# Sheet1.net
KiCad netlist of a schematic drawn in Altium Designer
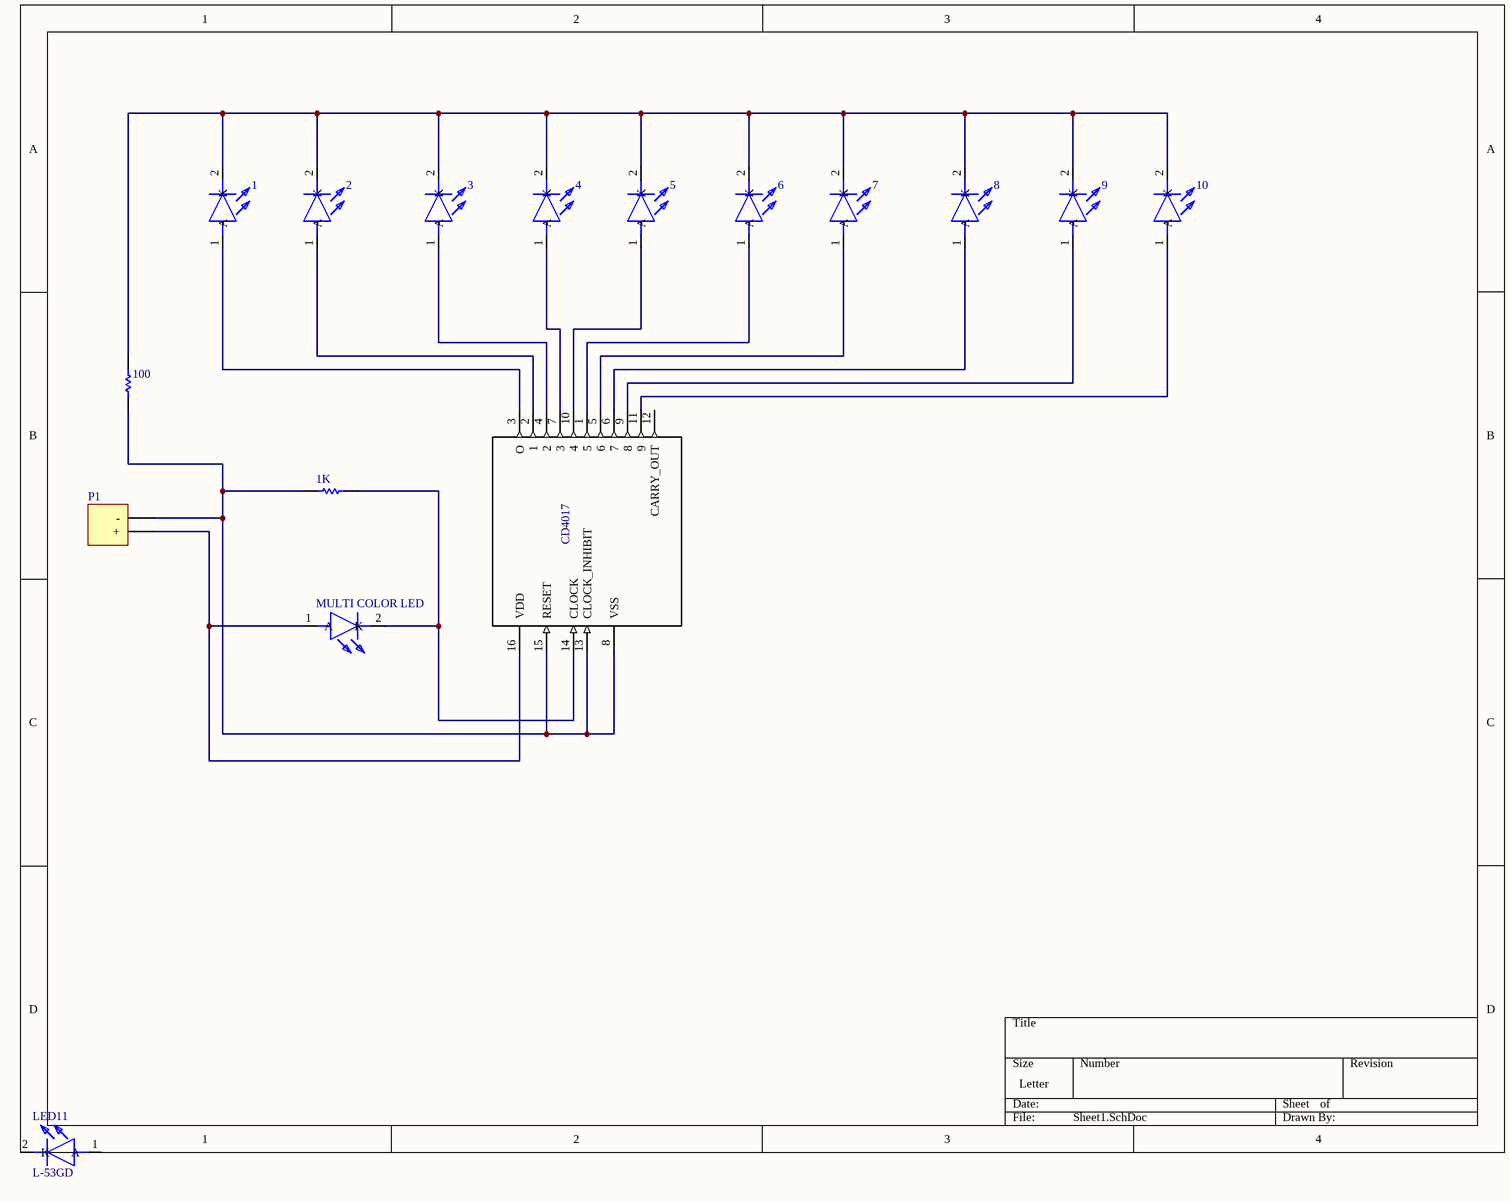
[diagram p0: Sheet1.SchDoc]

(export (version "E")
  (design (tool "Eeschema 10.0.6"))
  (components
    (comp (ref "1")
      (value "L-53GD")
      (footprint "SamacSys:L-53GD")
      (description "LED")
      (fields (field (name "RS PART NUMBER") "2286004A"))
      (libsource (lib "SamacSys") (part "L-53GD"))
    )
    (comp (ref "1K")
      (value "Res1")
      (footprint "AXIAL-0.3")
      (description "Resistor")
      (fields (field (name "PUBLISHER") "Altium Limited"))
      (libsource (lib "Miscellaneous Devices") (part "Res1"))
    )
    (comp (ref "2")
      (value "L-53GD")
      (footprint "SamacSys:L-53GD")
      (description "LED")
      (fields (field (name "RS PART NUMBER") "2286004A"))
      (libsource (lib "SamacSys") (part "L-53GD"))
    )
    (comp (ref "3")
      (value "L-53GD")
      (footprint "SamacSys:L-53GD")
      (description "LED")
      (fields (field (name "RS PART NUMBER") "2286004A"))
      (libsource (lib "SamacSys") (part "L-53GD"))
    )
    (comp (ref "4")
      (value "L-53GD")
      (footprint "SamacSys:L-53GD")
      (description "LED")
      (fields (field (name "RS PART NUMBER") "2286004A"))
      (libsource (lib "SamacSys") (part "L-53GD"))
    )
    (comp (ref "5")
      (value "L-53GD")
      (footprint "SamacSys:L-53GD")
      (description "LED")
      (fields (field (name "RS PART NUMBER") "2286004A"))
      (libsource (lib "SamacSys") (part "L-53GD"))
    )
    (comp (ref "6")
      (value "L-53GD")
      (footprint "SamacSys:L-53GD")
      (description "LED")
      (fields (field (name "RS PART NUMBER") "2286004A"))
      (libsource (lib "SamacSys") (part "L-53GD"))
    )
    (comp (ref "7")
      (value "L-53GD")
      (footprint "SamacSys:L-53GD")
      (description "LED")
      (fields (field (name "RS PART NUMBER") "2286004A"))
      (libsource (lib "SamacSys") (part "L-53GD"))
    )
    (comp (ref "8")
      (value "L-53GD")
      (footprint "SamacSys:L-53GD")
      (description "LED")
      (fields (field (name "RS PART NUMBER") "2286004A"))
      (libsource (lib "SamacSys") (part "L-53GD"))
    )
    (comp (ref "9")
      (value "L-53GD")
      (footprint "SamacSys:L-53GD")
      (description "LED")
      (fields (field (name "RS PART NUMBER") "2286004A"))
      (libsource (lib "SamacSys") (part "L-53GD"))
    )
    (comp (ref "10")
      (value "L-53GD")
      (footprint "SamacSys:L-53GD")
      (description "LED")
      (fields (field (name "RS PART NUMBER") "2286004A"))
      (libsource (lib "SamacSys") (part "L-53GD"))
    )
    (comp (ref "100")
      (value "Res1")
      (footprint "AXIAL-0.3")
      (description "Resistor")
      (fields (field (name "PUBLISHER") "Altium Limited"))
      (libsource (lib "Miscellaneous Devices") (part "Res1"))
    )
    (comp (ref "CD4017")
      (value "CD4017BE")
      (footprint "*DIP254P762X508-16")
      (description "IC Mos 4017/CD4017BE HARRIS")
      (fields (field (name "MF") "Texas"))
      (libsource (lib "CD4017BE") (part "CD4017BE"))
    )
    (comp (ref "LED11")
      (value "L-53GD")
      (footprint "SamacSys:L-53GD")
      (description "LED")
      (fields (field (name "RS PART NUMBER") "2286004A"))
      (libsource (lib "*") (part "L-53GD"))
    )
    (comp (ref "MULTI COLOR LED")
      (value "L-53GD")
      (footprint "SamacSys:L-53GD")
      (description "LED")
      (fields (field (name "RS PART NUMBER") "2286004A"))
      (libsource (lib "SamacSys") (part "L-53GD"))
    )
    (comp (ref "P1")
      (value "Header 2")
      (footprint "HDR1X2")
      (description "Header, 2-Pin")
      (fields (field (name "PUBLISHER") "Altium Limited"))
      (libsource (lib "Miscellaneous Connectors") (part "Header 2"))
    )
  )
  (nets
    (net (code "1") (name "Net-(1-A)") (class "Default")
      (node (ref "1") (pin "1") (pinfunction "A_1") (pintype "passive"))
      (node (ref "CD4017") (pin "3") (pinfunction "O_3") (pintype "output"))
    )
    (net (code "2") (name "Net-(1-K)") (class "Default")
      (node (ref "1") (pin "2") (pinfunction "K_2") (pintype "passive"))
      (node (ref "10") (pin "2") (pinfunction "K_2") (pintype "passive"))
      (node (ref "100") (pin "2") (pinfunction "2_2") (pintype "passive"))
      (node (ref "2") (pin "2") (pinfunction "K_2") (pintype "passive"))
      (node (ref "3") (pin "2") (pinfunction "K_2") (pintype "passive"))
      (node (ref "4") (pin "2") (pinfunction "K_2") (pintype "passive"))
      (node (ref "5") (pin "2") (pinfunction "K_2") (pintype "passive"))
      (node (ref "6") (pin "2") (pinfunction "K_2") (pintype "passive"))
      (node (ref "7") (pin "2") (pinfunction "K_2") (pintype "passive"))
      (node (ref "8") (pin "2") (pinfunction "K_2") (pintype "passive"))
      (node (ref "9") (pin "2") (pinfunction "K_2") (pintype "passive"))
    )
    (net (code "3") (name "Net-(2-A)") (class "Default")
      (node (ref "2") (pin "1") (pinfunction "A_1") (pintype "passive"))
      (node (ref "CD4017") (pin "2") (pinfunction "1_2") (pintype "output"))
    )
    (net (code "4") (name "Net-(3-A)") (class "Default")
      (node (ref "3") (pin "1") (pinfunction "A_1") (pintype "passive"))
      (node (ref "CD4017") (pin "4") (pinfunction "2_4") (pintype "output"))
    )
    (net (code "5") (name "Net-(4-A)") (class "Default")
      (node (ref "4") (pin "1") (pinfunction "A_1") (pintype "passive"))
      (node (ref "CD4017") (pin "7") (pinfunction "3_7") (pintype "output"))
    )
    (net (code "6") (name "Net-(5-A)") (class "Default")
      (node (ref "5") (pin "1") (pinfunction "A_1") (pintype "passive"))
      (node (ref "CD4017") (pin "10") (pinfunction "4_10") (pintype "output"))
    )
    (net (code "7") (name "Net-(6-A)") (class "Default")
      (node (ref "6") (pin "1") (pinfunction "A_1") (pintype "passive"))
      (node (ref "CD4017") (pin "1") (pinfunction "5_1") (pintype "output"))
    )
    (net (code "8") (name "Net-(7-A)") (class "Default")
      (node (ref "7") (pin "1") (pinfunction "A_1") (pintype "passive"))
      (node (ref "CD4017") (pin "5") (pinfunction "6_5") (pintype "output"))
    )
    (net (code "9") (name "Net-(8-A)") (class "Default")
      (node (ref "8") (pin "1") (pinfunction "A_1") (pintype "passive"))
      (node (ref "CD4017") (pin "6") (pinfunction "7_6") (pintype "output"))
    )
    (net (code "10") (name "Net-(9-A)") (class "Default")
      (node (ref "9") (pin "1") (pinfunction "A_1") (pintype "passive"))
      (node (ref "CD4017") (pin "9") (pinfunction "8_9") (pintype "output"))
    )
    (net (code "11") (name "Net-(10-A)") (class "Default")
      (node (ref "10") (pin "1") (pinfunction "A_1") (pintype "passive"))
      (node (ref "CD4017") (pin "11") (pinfunction "9_11") (pintype "output"))
    )
    (net (code "12") (name "Net-(CD4017-CLOCK)") (class "Default")
      (node (ref "1K") (pin "2") (pinfunction "2_2") (pintype "passive"))
      (node (ref "CD4017") (pin "14") (pinfunction "CLOCK_14") (pintype "input"))
      (node (ref "MULTI COLOR LED") (pin "2") (pinfunction "K_2") (pintype "passive"))
    )
    (net (code "13") (name "Net-(CD4017-CLOCK_INHIBIT)") (class "Default")
      (node (ref "100") (pin "1") (pinfunction "1_1") (pintype "passive"))
      (node (ref "1K") (pin "1") (pinfunction "1_1") (pintype "passive"))
      (node (ref "CD4017") (pin "13") (pinfunction "CLOCK_INHIBIT_13") (pintype "input"))
      (node (ref "CD4017") (pin "15") (pinfunction "RESET_15") (pintype "input"))
      (node (ref "CD4017") (pin "8") (pinfunction "VSS_8") (pintype "power_in"))
      (node (ref "P1") (pin "2") (pinfunction "-_2") (pintype "passive"))
    )
    (net (code "14") (name "Net-(CD4017-VDD)") (class "Default")
      (node (ref "CD4017") (pin "16") (pinfunction "VDD_16") (pintype "power_in"))
      (node (ref "MULTI COLOR LED") (pin "1") (pinfunction "A_1") (pintype "passive"))
      (node (ref "P1") (pin "1") (pinfunction "+_1") (pintype "passive"))
    )
    (net (code "15") (name "unconnected-(CD4017-CARRY_OUT-Pad12)") (class "Default")
      (node (ref "CD4017") (pin "12") (pinfunction "CARRY_OUT_12") (pintype "output"))
    )
    (net (code "16") (name "unconnected-(LED11-A-Pad1)") (class "Default")
      (node (ref "LED11") (pin "1") (pinfunction "A_1") (pintype "passive"))
    )
    (net (code "17") (name "unconnected-(LED11-K-Pad2)") (class "Default")
      (node (ref "LED11") (pin "2") (pinfunction "K_2") (pintype "passive"))
    )
  )
)
